# LDO_5V.net
KiCad netlist of a schematic drawn in Altium Designer
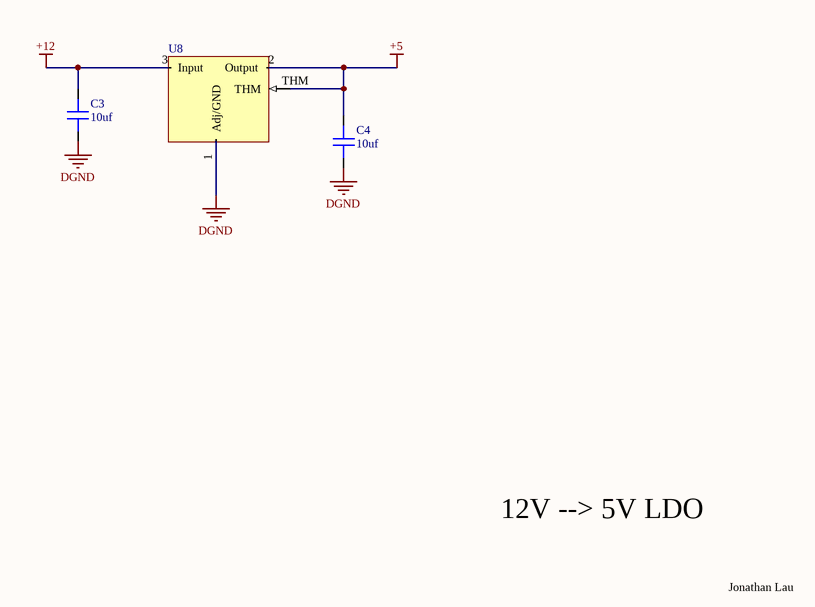
[diagram p0: LDO_5V.SchDoc]

(export (version "E")
  (design (tool "Eeschema 10.0.6"))
  (components
    (comp (ref "C3")
      (value "10uf")
      (footprint "CAP 0805/2012")
      (fields
        (field (name "Comment") "Capacitor MLCC 10uf 16V CAP 0805/2012")
        (field (name "CREATED_BY") "Nick Mah")
      )
      (libsource (lib "Altium-Lib") (part "Capacitor"))
    )
    (comp (ref "C4")
      (value "10uf")
      (footprint "CAP 0805/2012")
      (fields
        (field (name "Comment") "Capacitor MLCC 10uf 16V CAP 0805/2012")
        (field (name "CREATED_BY") "Nick Mah")
      )
      (libsource (lib "Altium-Lib") (part "Capacitor"))
    )
    (comp (ref "U8")
      (value "NCP1117ST50T3G")
      (footprint "SOT-223-3")
      (description "Linear Voltage Regulator IC Positive Fixed 1 Output 5V 1A SOT-223")
      (fields (field (name "CREATED_BY") "Angel Delgado"))
      (libsource (lib "Altium-Lib") (part "NCP1117ST50T3G"))
    )
  )
  (nets
    (net (code "1") (name "+5") (class "Default")
      (node (ref "C4") (pin "2") (pinfunction "2_2") (pintype "passive"))
      (node (ref "U8") (pin "2") (pinfunction "Output_2") (pintype "input"))
      (node (ref "U8") (pin "THM") (pinfunction "THM_THM") (pintype "input"))
    )
    (net (code "2") (name "+12") (class "Default")
      (node (ref "C3") (pin "2") (pinfunction "2_2") (pintype "passive"))
      (node (ref "U8") (pin "3") (pinfunction "Input_3") (pintype "input"))
    )
    (net (code "3") (name "DGND") (class "Default")
      (node (ref "C3") (pin "1") (pinfunction "1_1") (pintype "passive"))
      (node (ref "C4") (pin "1") (pinfunction "1_1") (pintype "passive"))
      (node (ref "U8") (pin "1") (pinfunction "Adj/GND_1") (pintype "input"))
    )
  )
)
